# vssb.net
KiCad netlist of a schematic drawn in EAGLE
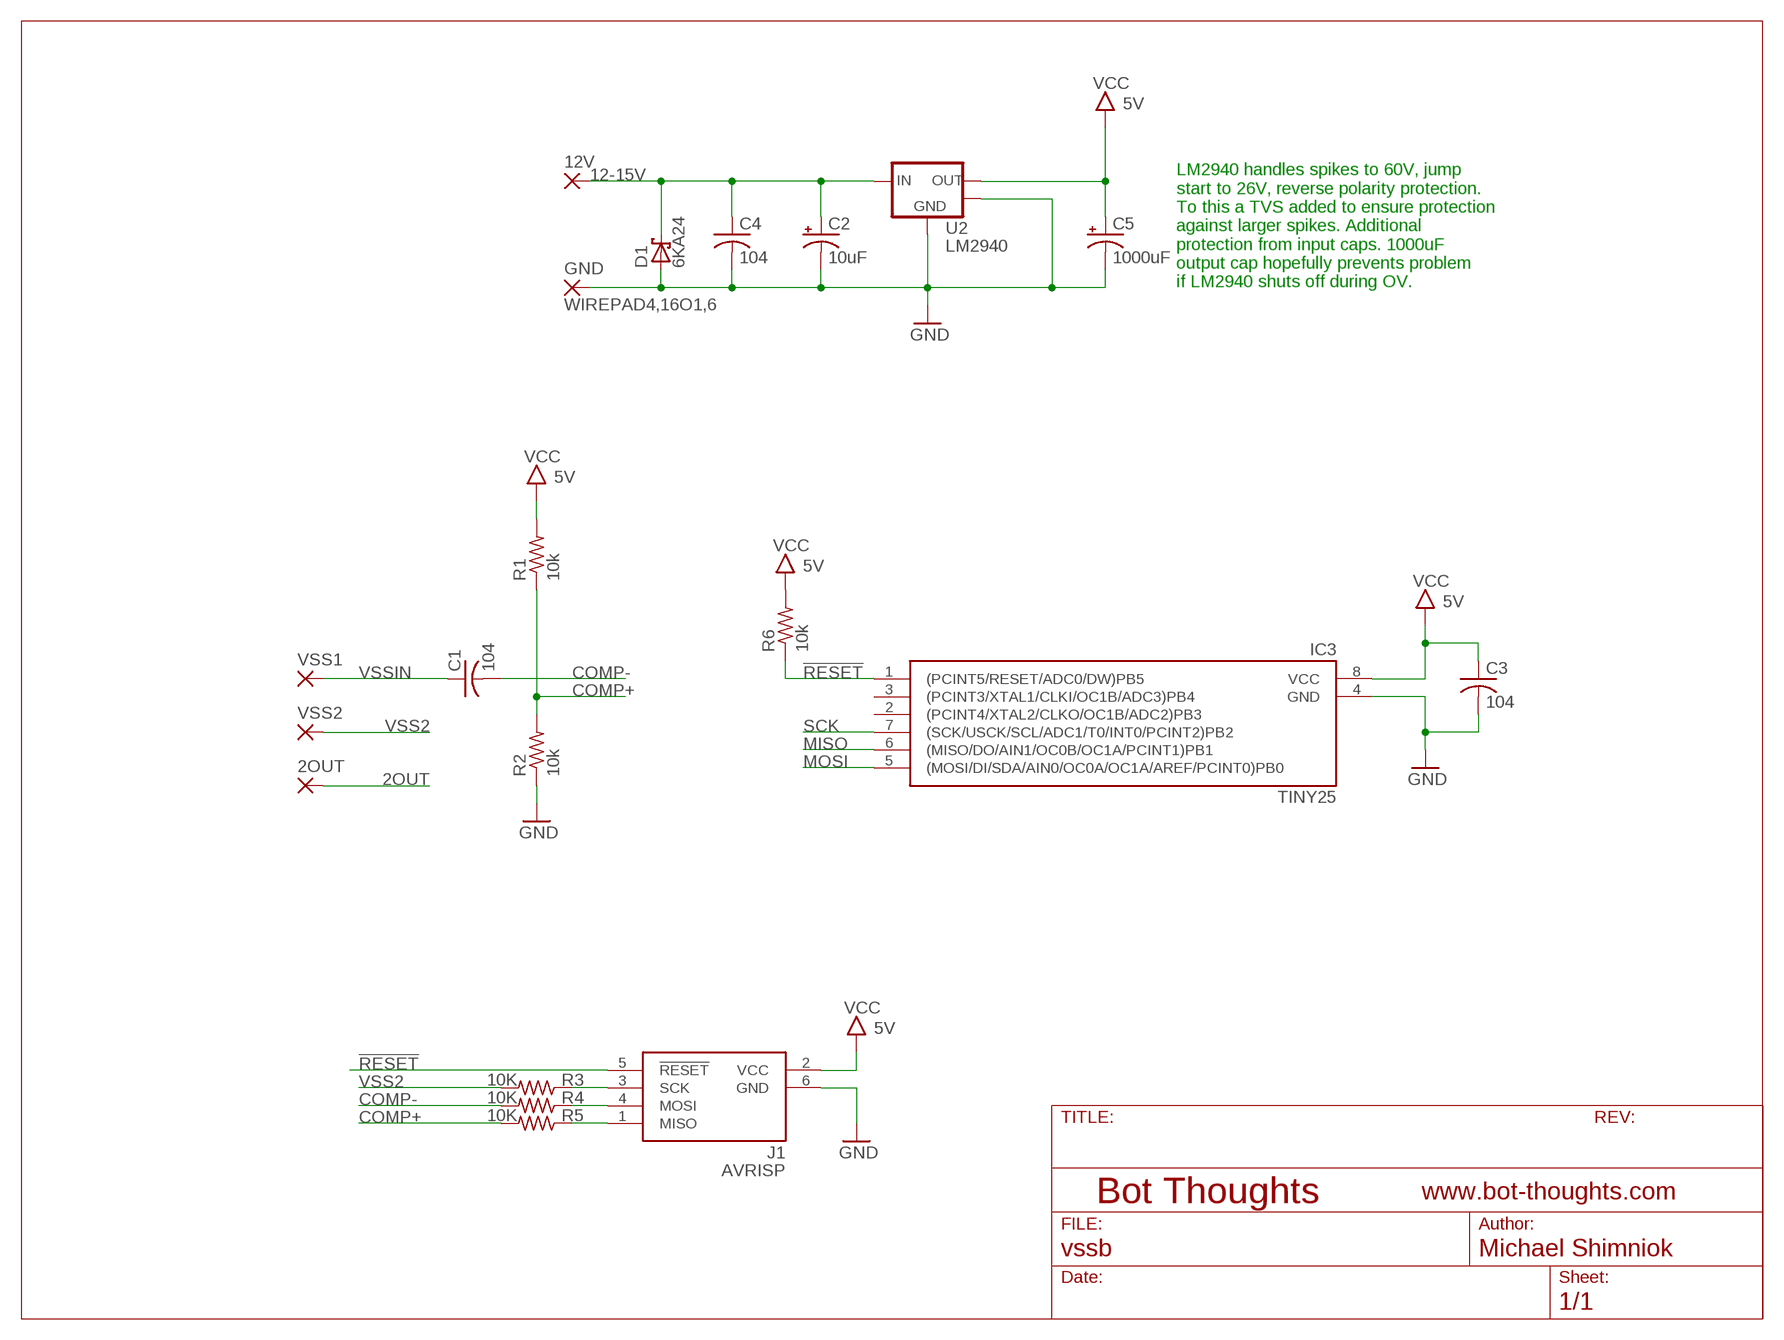
[diagram p0: schematic, sheet 1]

(export (version "E")
  (design (tool "Eeschema 10.0.6"))
  (components
    (comp (ref "2OUT")
      (value "WIREPAD4,16O1,6")
      (footprint "eagle-import:4,16O1,6")
      (libsource (lib "eagle-import") (part "WIREPAD4,16O1,6"))
    )
    (comp (ref "12V")
      (value "WIREPAD4,16O1,6")
      (footprint "eagle-import:4,16O1,6")
      (libsource (lib "eagle-import") (part "WIREPAD4,16O1,6"))
    )
    (comp (ref "C1")
      (value "104")
      (footprint "eagle-import:C050-024X044")
      (libsource (lib "eagle-import") (part "C-US050-024X044"))
    )
    (comp (ref "C2")
      (value "10uF")
      (footprint "eagle-import:E2,5-6")
      (libsource (lib "eagle-import") (part "CPOL-USE2.5-6"))
    )
    (comp (ref "C3")
      (value "104")
      (footprint "eagle-import:C0603")
      (libsource (lib "eagle-import") (part "C-USC0603"))
    )
    (comp (ref "C4")
      (value "104")
      (footprint "eagle-import:C0603")
      (libsource (lib "eagle-import") (part "C-USC0603"))
    )
    (comp (ref "C5")
      (value "1000uF")
      (footprint "eagle-import:E5-13")
      (libsource (lib "eagle-import") (part "CPOL-USE5-13"))
    )
    (comp (ref "D1")
      (value "6KA24")
      (footprint "eagle-import:P600")
      (libsource (lib "eagle-import") (part "6KA24_P600"))
    )
    (comp (ref "GND")
      (value "WIREPAD4,16O1,6")
      (footprint "eagle-import:4,16O1,6")
      (libsource (lib "eagle-import") (part "WIREPAD4,16O1,6"))
    )
    (comp (ref "IC3")
      (value "TINY25")
      (footprint "eagle-import:SOIC8N")
      (libsource (lib "eagle-import") (part "TINY25/45/85-20SSU"))
    )
    (comp (ref "J1")
      (value "AVRISP")
      (footprint "eagle-import:CON6P2R")
      (libsource (lib "eagle-import") (part "AVRISP6_COMPACT"))
    )
    (comp (ref "R1")
      (value "10k")
      (footprint "eagle-import:R0603")
      (libsource (lib "eagle-import") (part "R-US_R0603"))
    )
    (comp (ref "R2")
      (value "10k")
      (footprint "eagle-import:R0603")
      (libsource (lib "eagle-import") (part "R-US_R0603"))
    )
    (comp (ref "R3")
      (value "10K")
      (footprint "eagle-import:R0603")
      (libsource (lib "eagle-import") (part "R-US_R0603"))
    )
    (comp (ref "R4")
      (value "10K")
      (footprint "eagle-import:R0603")
      (libsource (lib "eagle-import") (part "R-US_R0603"))
    )
    (comp (ref "R5")
      (value "10K")
      (footprint "eagle-import:R0603")
      (libsource (lib "eagle-import") (part "R-US_R0603"))
    )
    (comp (ref "R6")
      (value "10k")
      (footprint "eagle-import:R0603")
      (libsource (lib "eagle-import") (part "R-US_R0603"))
    )
    (comp (ref "U2")
      (value "LM2940")
      (footprint "eagle-import:SOT-223-3")
      (libsource (lib "eagle-import") (part "LM2940DCY"))
    )
    (comp (ref "VSS1")
      (value "WIREPAD4,16O1,6")
      (footprint "eagle-import:4,16O1,6")
      (libsource (lib "eagle-import") (part "WIREPAD4,16O1,6"))
    )
    (comp (ref "VSS2")
      (value "WIREPAD4,16O1,6")
      (footprint "eagle-import:4,16O1,6")
      (libsource (lib "eagle-import") (part "WIREPAD4,16O1,6"))
    )
  )
  (nets
    (net (code "1") (name "/2OUT") (class "Default")
      (node (ref "2OUT") (pin "1") (pinfunction "P_1") (pintype "passive"))
    )
    (net (code "2") (name "/12-15V") (class "Default")
      (node (ref "12V") (pin "1") (pinfunction "P_1") (pintype "passive"))
      (node (ref "C2") (pin "+") (pinfunction "+_+") (pintype "passive"))
      (node (ref "C4") (pin "1") (pinfunction "1_1") (pintype "passive"))
      (node (ref "D1") (pin "C") (pinfunction "C_C") (pintype "passive"))
      (node (ref "U2") (pin "1") (pinfunction "VIN_1") (pintype "bidirectional"))
    )
    (net (code "3") (name "/COMP+") (class "Default")
      (node (ref "R1") (pin "1") (pinfunction "1_1") (pintype "passive"))
      (node (ref "R2") (pin "2") (pinfunction "2_2") (pintype "passive"))
      (node (ref "R5") (pin "2") (pinfunction "2_2") (pintype "passive"))
    )
    (net (code "4") (name "/COMP-") (class "Default")
      (node (ref "C1") (pin "2") (pinfunction "2_2") (pintype "passive"))
      (node (ref "R4") (pin "2") (pinfunction "2_2") (pintype "passive"))
    )
    (net (code "5") (name "/MISO") (class "Default")
      (node (ref "IC3") (pin "6") (pinfunction "(MISO/DO/AIN1/OC0B/OC1A/PCINT1)PB1_6") (pintype "bidirectional"))
      (node (ref "J1") (pin "1") (pinfunction "MISO_1") (pintype "input"))
      (node (ref "R5") (pin "1") (pinfunction "1_1") (pintype "passive"))
    )
    (net (code "6") (name "/MOSI") (class "Default")
      (node (ref "IC3") (pin "5") (pinfunction "(MOSI/DI/SDA/AIN0/OC0A/OC1A/AREF/PCINT0)PB0_5") (pintype "bidirectional"))
      (node (ref "J1") (pin "4") (pinfunction "MOSI_4") (pintype "output"))
      (node (ref "R4") (pin "1") (pinfunction "1_1") (pintype "passive"))
    )
    (net (code "7") (name "/SCK") (class "Default")
      (node (ref "IC3") (pin "7") (pinfunction "(SCK/USCK/SCL/ADC1/T0/INT0/PCINT2)PB2_7") (pintype "bidirectional"))
      (node (ref "J1") (pin "3") (pinfunction "SCK_3") (pintype "output"))
      (node (ref "R3") (pin "1") (pinfunction "1_1") (pintype "passive"))
    )
    (net (code "8") (name "/VSS2") (class "Default")
      (node (ref "R3") (pin "2") (pinfunction "2_2") (pintype "passive"))
      (node (ref "VSS2") (pin "1") (pinfunction "P_1") (pintype "passive"))
    )
    (net (code "9") (name "/VSSIN") (class "Default")
      (node (ref "C1") (pin "1") (pinfunction "1_1") (pintype "passive"))
      (node (ref "VSS1") (pin "1") (pinfunction "P_1") (pintype "passive"))
    )
    (net (code "10") (name "/~{RESET}") (class "Default")
      (node (ref "IC3") (pin "1") (pinfunction "(PCINT5/RESET/ADC0/DW)PB5_1") (pintype "bidirectional"))
      (node (ref "J1") (pin "5") (pinfunction "~{RESET}_5") (pintype "output"))
      (node (ref "R6") (pin "1") (pinfunction "1_1") (pintype "passive"))
    )
    (net (code "11") (name "5V") (class "Default")
      (node (ref "C3") (pin "1") (pinfunction "1_1") (pintype "passive"))
      (node (ref "C5") (pin "+") (pinfunction "+_+") (pintype "passive"))
      (node (ref "IC3") (pin "8") (pinfunction "VCC_8") (pintype "power_in"))
      (node (ref "J1") (pin "2") (pinfunction "VCC_2") (pintype "power_in"))
      (node (ref "R1") (pin "2") (pinfunction "2_2") (pintype "passive"))
      (node (ref "R6") (pin "2") (pinfunction "2_2") (pintype "passive"))
      (node (ref "U2") (pin "3") (pinfunction "VOUT_3") (pintype "bidirectional"))
    )
    (net (code "12") (name "GND") (class "Default")
      (node (ref "C2") (pin "-") (pinfunction "-_-") (pintype "passive"))
      (node (ref "C3") (pin "2") (pinfunction "2_2") (pintype "passive"))
      (node (ref "C4") (pin "2") (pinfunction "2_2") (pintype "passive"))
      (node (ref "C5") (pin "-") (pinfunction "-_-") (pintype "passive"))
      (node (ref "D1") (pin "A") (pinfunction "A_A") (pintype "passive"))
      (node (ref "GND") (pin "1") (pinfunction "P_1") (pintype "passive"))
      (node (ref "IC3") (pin "4") (pinfunction "GND_4") (pintype "power_in"))
      (node (ref "J1") (pin "6") (pinfunction "GND_6") (pintype "power_in"))
      (node (ref "R2") (pin "1") (pinfunction "1_1") (pintype "passive"))
      (node (ref "U2") (pin "2") (pinfunction "GND_2") (pintype "bidirectional"))
      (node (ref "U2") (pin "4") (pinfunction "TAB_4") (pintype "bidirectional"))
    )
    (net (code "13") (name "unconnected-(IC3-(PCINT3{slash}XTAL1{slash}CLKI{slash}OC1B{slash}ADC3)PB4-Pad3)") (class "Default")
      (node (ref "IC3") (pin "3") (pinfunction "(PCINT3/XTAL1/CLKI/OC1B/ADC3)PB4_3") (pintype "bidirectional"))
    )
    (net (code "14") (name "unconnected-(IC3-(PCINT4{slash}XTAL2{slash}CLKO{slash}OC1B{slash}ADC2)PB3-Pad2)") (class "Default")
      (node (ref "IC3") (pin "2") (pinfunction "(PCINT4/XTAL2/CLKO/OC1B/ADC2)PB3_2") (pintype "bidirectional"))
    )
  )
)
